# Baja_Sensors.net
KiCad netlist of a schematic drawn in EAGLE
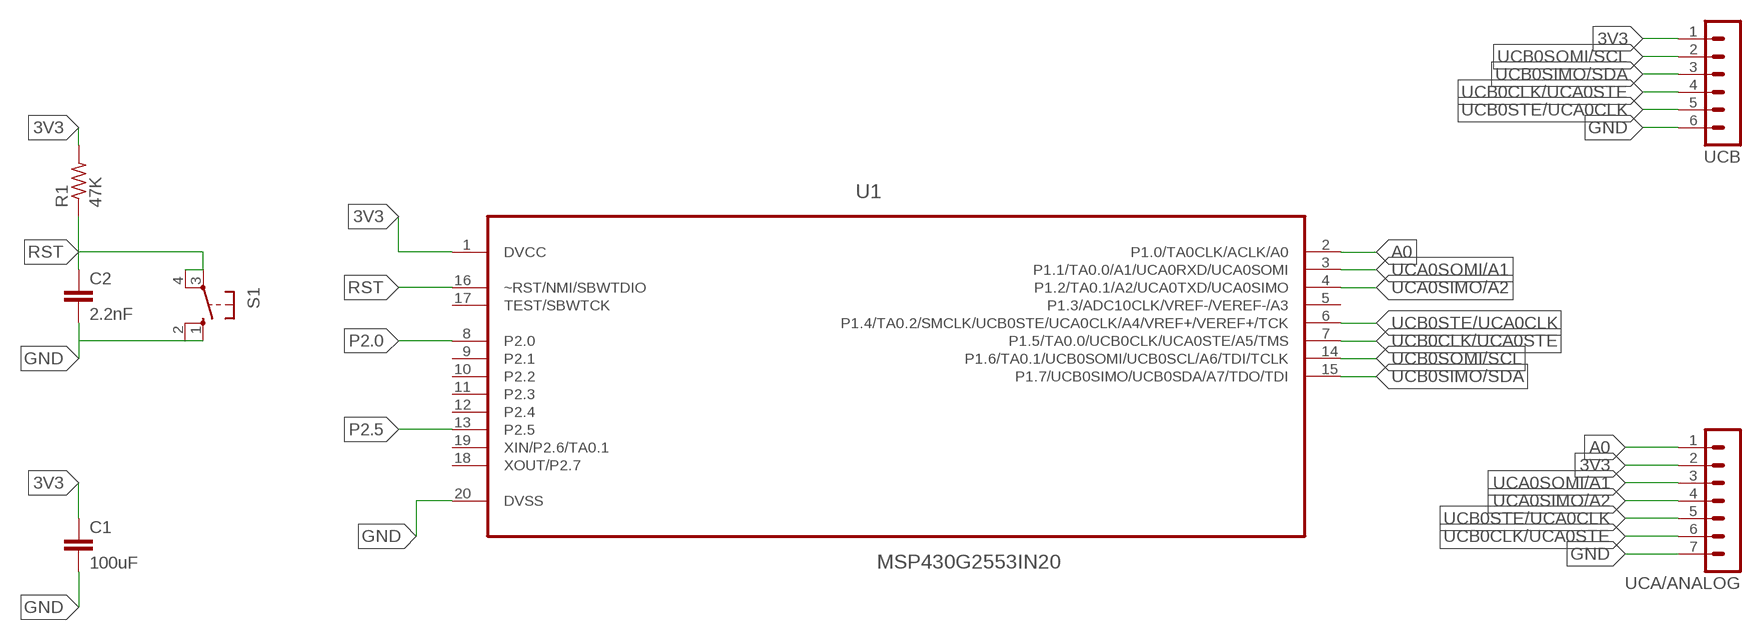
[diagram p0: schematic, sheet 1]

(export (version "E")
  (design (tool "Eeschema 10.0.6"))
  (components
    (comp (ref "C1")
      (value "100uF")
      (footprint "eagle-import:C5B5")
      (libsource (lib "eagle-import") (part "C5/5"))
    )
    (comp (ref "C2")
      (value "2.2nF")
      (footprint "eagle-import:C5B3")
      (libsource (lib "eagle-import") (part "C5/3"))
    )
    (comp (ref "R1")
      (value "47K")
      (footprint "eagle-import:0207_5V")
      (libsource (lib "eagle-import") (part "R-US_0207/5V"))
    )
    (comp (ref "S1")
      (value "10-XX")
      (footprint "eagle-import:B3F-10XX")
      (fields (field (name "MPN") "B3F-1000"))
      (libsource (lib "eagle-import") (part "10-XX"))
    )
    (comp (ref "U1")
      (value "MSP430G2553IN20")
      (footprint "eagle-import:DIP254P762X508-20")
      (fields (field (name "MPN") "MSP430G2332IN20"))
      (libsource (lib "eagle-import") (part "MSP430G2553IN20"))
    )
    (comp (ref "UCA/ANALOG")
      (value "MA07-1")
      (footprint "eagle-import:MA07-1")
      (libsource (lib "eagle-import") (part "MA07-1"))
    )
    (comp (ref "UCB")
      (value "MA06-1")
      (footprint "eagle-import:MA06-1")
      (libsource (lib "eagle-import") (part "MA06-1"))
    )
  )
  (nets
    (net (code "1") (name "3V3") (class "Default")
      (node (ref "C1") (pin "1") (pinfunction "1_1") (pintype "passive"))
      (node (ref "R1") (pin "2") (pinfunction "2_2") (pintype "passive"))
      (node (ref "U1") (pin "1") (pinfunction "DVCC_1") (pintype "power_in"))
      (node (ref "UCA/ANALOG") (pin "2") (pinfunction "2_2") (pintype "passive"))
      (node (ref "UCB") (pin "1") (pinfunction "1_1") (pintype "passive"))
    )
    (net (code "2") (name "A0") (class "Default")
      (node (ref "U1") (pin "2") (pinfunction "P1.0/TA0CLK/ACLK/A0_2") (pintype "bidirectional"))
      (node (ref "UCA/ANALOG") (pin "1") (pinfunction "1_1") (pintype "passive"))
    )
    (net (code "3") (name "GND") (class "Default")
      (node (ref "C1") (pin "2") (pinfunction "2_2") (pintype "passive"))
      (node (ref "C2") (pin "2") (pinfunction "2_2") (pintype "passive"))
      (node (ref "S1") (pin "1") (pinfunction "S_1") (pintype "passive"))
      (node (ref "S1") (pin "2") (pinfunction "S1_2") (pintype "passive"))
      (node (ref "U1") (pin "20") (pinfunction "DVSS_20") (pintype "power_in"))
      (node (ref "UCA/ANALOG") (pin "7") (pinfunction "7_7") (pintype "passive"))
      (node (ref "UCB") (pin "6") (pinfunction "6_6") (pintype "passive"))
    )
    (net (code "4") (name "P2.0") (class "Default")
      (node (ref "U1") (pin "8") (pinfunction "P2.0_8") (pintype "bidirectional"))
    )
    (net (code "5") (name "P2.5") (class "Default")
      (node (ref "U1") (pin "13") (pinfunction "P2.5_13") (pintype "bidirectional"))
    )
    (net (code "6") (name "RST") (class "Default")
      (node (ref "C2") (pin "1") (pinfunction "1_1") (pintype "passive"))
      (node (ref "R1") (pin "1") (pinfunction "1_1") (pintype "passive"))
      (node (ref "S1") (pin "3") (pinfunction "P_3") (pintype "passive"))
      (node (ref "S1") (pin "4") (pinfunction "P1_4") (pintype "passive"))
      (node (ref "U1") (pin "16") (pinfunction "~{RST/NMI/SBWTDIO}_16") (pintype "input"))
    )
    (net (code "7") (name "UCA0SIMO{slash}A2") (class "Default")
      (node (ref "U1") (pin "4") (pinfunction "P1.2/TA0.1/A2/UCA0TXD/UCA0SIMO_4") (pintype "bidirectional"))
      (node (ref "UCA/ANALOG") (pin "4") (pinfunction "4_4") (pintype "passive"))
    )
    (net (code "8") (name "UCA0SOMI{slash}A1") (class "Default")
      (node (ref "U1") (pin "3") (pinfunction "P1.1/TA0.0/A1/UCA0RXD/UCA0SOMI_3") (pintype "bidirectional"))
      (node (ref "UCA/ANALOG") (pin "3") (pinfunction "3_3") (pintype "passive"))
    )
    (net (code "9") (name "UCB0CLK{slash}UCA0STE") (class "Default")
      (node (ref "U1") (pin "7") (pinfunction "P1.5/TA0.0/UCB0CLK/UCA0STE/A5/TMS_7") (pintype "bidirectional"))
      (node (ref "UCA/ANALOG") (pin "6") (pinfunction "6_6") (pintype "passive"))
      (node (ref "UCB") (pin "4") (pinfunction "4_4") (pintype "passive"))
    )
    (net (code "10") (name "UCB0SIMO{slash}SDA") (class "Default")
      (node (ref "U1") (pin "15") (pinfunction "P1.7/UCB0SIMO/UCB0SDA/A7/TDO/TDI_15") (pintype "bidirectional"))
      (node (ref "UCB") (pin "3") (pinfunction "3_3") (pintype "passive"))
    )
    (net (code "11") (name "UCB0SOMI{slash}SCL") (class "Default")
      (node (ref "U1") (pin "14") (pinfunction "P1.6/TA0.1/UCB0SOMI/UCB0SCL/A6/TDI/TCLK_14") (pintype "bidirectional"))
      (node (ref "UCB") (pin "2") (pinfunction "2_2") (pintype "passive"))
    )
    (net (code "12") (name "UCB0STE{slash}UCA0CLK") (class "Default")
      (node (ref "U1") (pin "6") (pinfunction "P1.4/TA0.2/SMCLK/UCB0STE/UCA0CLK/A4/VREF+/VEREF+/TCK_6") (pintype "bidirectional"))
      (node (ref "UCA/ANALOG") (pin "5") (pinfunction "5_5") (pintype "passive"))
      (node (ref "UCB") (pin "5") (pinfunction "5_5") (pintype "passive"))
    )
    (net (code "13") (name "unconnected-(U1-P1.3{slash}ADC10CLK{slash}VREF-{slash}VEREF-{slash}A3-Pad5)") (class "Default")
      (node (ref "U1") (pin "5") (pinfunction "P1.3/ADC10CLK/VREF-/VEREF-/A3_5") (pintype "bidirectional"))
    )
    (net (code "14") (name "unconnected-(U1-P2.1-Pad9)") (class "Default")
      (node (ref "U1") (pin "9") (pinfunction "P2.1_9") (pintype "bidirectional"))
    )
    (net (code "15") (name "unconnected-(U1-P2.2-Pad10)") (class "Default")
      (node (ref "U1") (pin "10") (pinfunction "P2.2_10") (pintype "bidirectional"))
    )
    (net (code "16") (name "unconnected-(U1-P2.3-Pad11)") (class "Default")
      (node (ref "U1") (pin "11") (pinfunction "P2.3_11") (pintype "bidirectional"))
    )
    (net (code "17") (name "unconnected-(U1-P2.4-Pad12)") (class "Default")
      (node (ref "U1") (pin "12") (pinfunction "P2.4_12") (pintype "bidirectional"))
    )
    (net (code "18") (name "unconnected-(U1-TEST{slash}SBWTCK-Pad17)") (class "Default")
      (node (ref "U1") (pin "17") (pinfunction "TEST/SBWTCK_17") (pintype "input"))
    )
    (net (code "19") (name "unconnected-(U1-XIN{slash}P2.6{slash}TA0.1-Pad19)") (class "Default")
      (node (ref "U1") (pin "19") (pinfunction "XIN/P2.6/TA0.1_19") (pintype "bidirectional"))
    )
    (net (code "20") (name "unconnected-(U1-XOUT{slash}P2.7-Pad18)") (class "Default")
      (node (ref "U1") (pin "18") (pinfunction "XOUT/P2.7_18") (pintype "bidirectional"))
    )
  )
)
